# UPCNSL-ABS-PVC-2A.net
KiCad netlist of a schematic drawn in Altium Designer
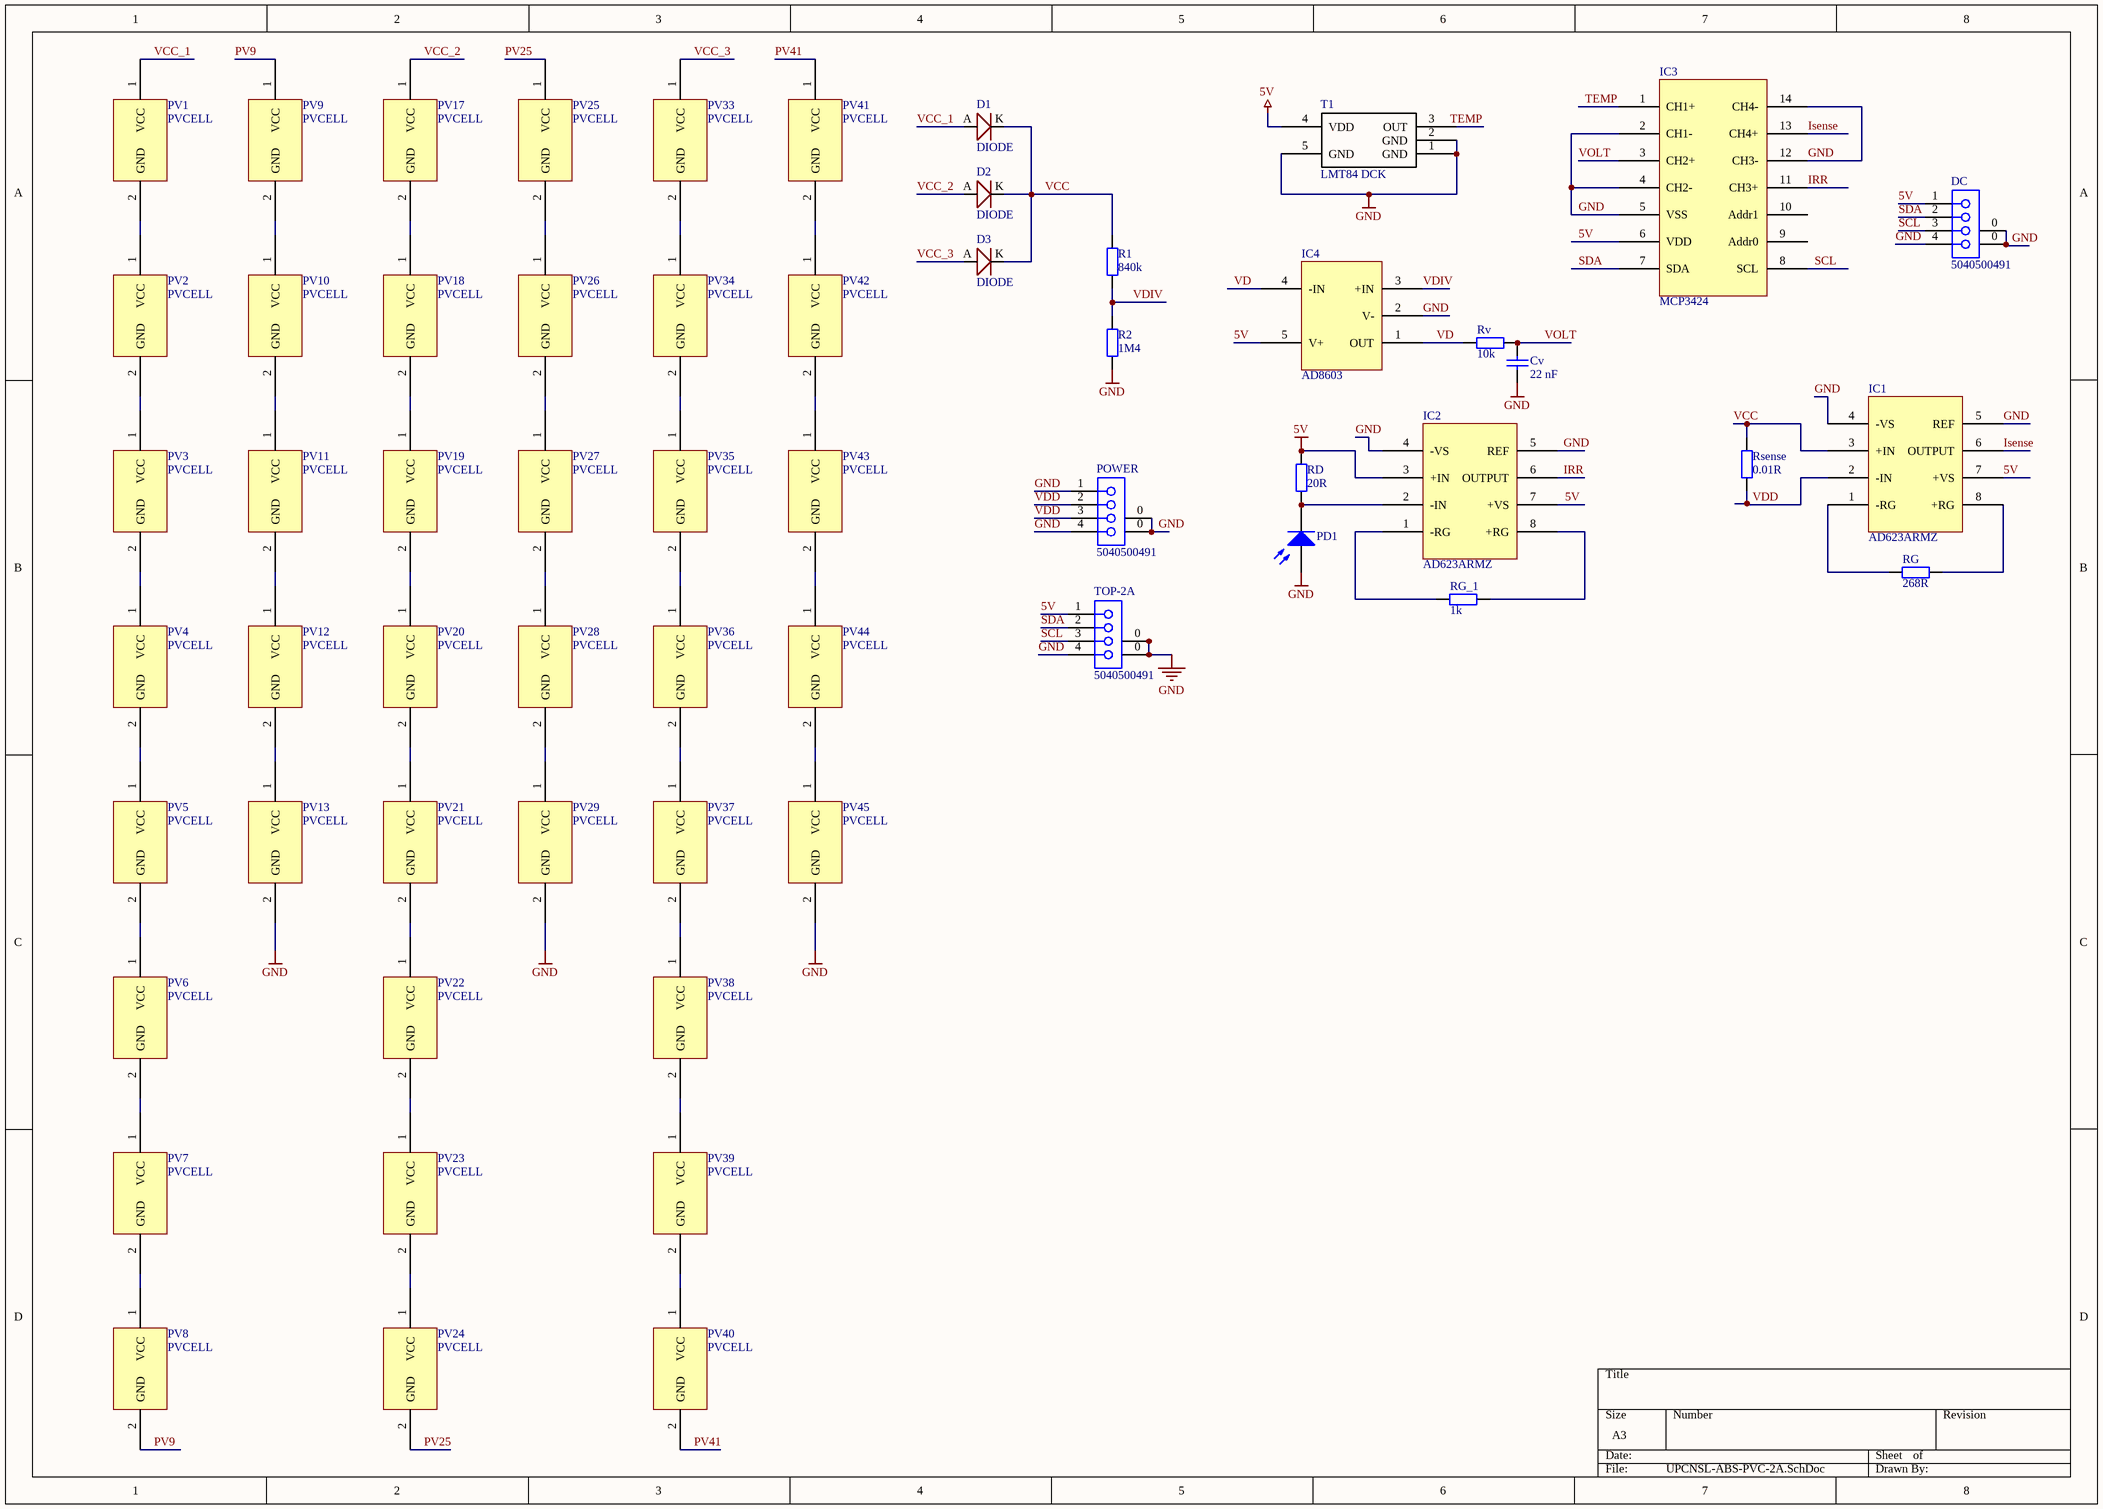
[diagram p0: UPCNSL-ABS-PVC-2A.SchDoc]

(export (version "E")
  (design (tool "Eeschema 10.0.6"))
  (components
    (comp (ref "Cv")
      (value "22 nF")
      (footprint "CAP0603")
      (description "Capacitor")
      (fields (field (name "Comment") "CAP0603"))
      (libsource (lib "UPCNSL-ABS-FLS-ARD_v1.2") (part "CAP0603"))
    )
    (comp (ref "D1")
      (value "DIODE")
      (footprint "(Schottky diode) SODFL160X70-2N")
      (libsource (lib "UPCNSL-ABS-FLS-ARD_v1.2") (part "DIODE"))
    )
    (comp (ref "D2")
      (value "DIODE")
      (footprint "(Schottky diode) SODFL160X70-2N")
      (libsource (lib "UPCNSL-ABS-FLS-ARD_v1.2") (part "DIODE"))
    )
    (comp (ref "D3")
      (value "DIODE")
      (footprint "(Schottky diode) SODFL160X70-2N")
      (libsource (lib "UPCNSL-ABS-FLS-ARD_v1.2") (part "DIODE"))
    )
    (comp (ref "DC")
      (value "5040500491")
      (footprint "5040500491")
      (libsource (lib "3CAT_Connectors") (part "MOLEX_5040500491"))
    )
    (comp (ref "IC1")
      (value "AD623ARMZ")
      (footprint "AD623ARMZ")
      (libsource (lib "UPCNSL-ABS-FLS-PVC") (part "AD623ARMZ"))
    )
    (comp (ref "IC2")
      (value "AD623ARMZ")
      (footprint "AD623ARMZ")
      (libsource (lib "UPCNSL-ABS-FLS-PVC") (part "AD623ARMZ"))
    )
    (comp (ref "IC3")
      (value "MCP3424")
      (footprint "MCP3424")
      (description "18-Bit, Multi-Channel ΔΣ Analog-to-Digital Converter with  I2C")
      (libsource (lib "UPCNSL-ABS-FLS-PVC") (part "MCP3424"))
    )
    (comp (ref "IC4")
      (value "AD8603")
      (footprint "AD8603")
      (libsource (lib "UPCNSL-ABS-FLS-PVC") (part "AD8603"))
    )
    (comp (ref "PD1")
      (value "Photo Sen")
      (footprint "C0805")
      (description "Photosensitive Diode")
      (fields (field (name "PUBLISHER") "Altium Limited"))
      (libsource (lib "Miscellaneous Devices") (part "Photo Sen"))
    )
    (comp (ref "POWER")
      (value "5040500491")
      (footprint "5040500491")
      (libsource (lib "3CAT_Connectors") (part "MOLEX_5040500491"))
    )
    (comp (ref "PV1")
      (value "PVCELL")
      (footprint "PV CELLS")
      (description "IXYS KXOB22-12X1L-ND")
      (libsource (lib "UPCNSL-ABS-FLS-PVC") (part "PVCELLS"))
    )
    (comp (ref "PV2")
      (value "PVCELL")
      (footprint "PV CELLS")
      (description "IXYS KXOB22-12X1L-ND")
      (libsource (lib "UPCNSL-ABS-FLS-PVC") (part "PVCELLS"))
    )
    (comp (ref "PV3")
      (value "PVCELL")
      (footprint "PV CELLS")
      (description "IXYS KXOB22-12X1L-ND")
      (libsource (lib "UPCNSL-ABS-FLS-PVC") (part "PVCELLS"))
    )
    (comp (ref "PV4")
      (value "PVCELL")
      (footprint "PV CELLS")
      (description "IXYS KXOB22-12X1L-ND")
      (libsource (lib "UPCNSL-ABS-FLS-PVC") (part "PVCELLS"))
    )
    (comp (ref "PV5")
      (value "PVCELL")
      (footprint "PV CELLS")
      (description "IXYS KXOB22-12X1L-ND")
      (libsource (lib "UPCNSL-ABS-FLS-PVC") (part "PVCELLS"))
    )
    (comp (ref "PV6")
      (value "PVCELL")
      (footprint "PV CELLS")
      (description "IXYS KXOB22-12X1L-ND")
      (libsource (lib "UPCNSL-ABS-FLS-PVC") (part "PVCELLS"))
    )
    (comp (ref "PV7")
      (value "PVCELL")
      (footprint "PV CELLS")
      (description "IXYS KXOB22-12X1L-ND")
      (libsource (lib "UPCNSL-ABS-FLS-PVC") (part "PVCELLS"))
    )
    (comp (ref "PV8")
      (value "PVCELL")
      (footprint "PV CELLS")
      (description "IXYS KXOB22-12X1L-ND")
      (libsource (lib "UPCNSL-ABS-FLS-PVC") (part "PVCELLS"))
    )
    (comp (ref "PV9")
      (value "PVCELL")
      (footprint "PV CELLS")
      (description "IXYS KXOB22-12X1L-ND")
      (libsource (lib "UPCNSL-ABS-FLS-PVC") (part "PVCELLS"))
    )
    (comp (ref "PV10")
      (value "PVCELL")
      (footprint "PV CELLS")
      (description "IXYS KXOB22-12X1L-ND")
      (libsource (lib "UPCNSL-ABS-FLS-PVC") (part "PVCELLS"))
    )
    (comp (ref "PV11")
      (value "PVCELL")
      (footprint "PV CELLS")
      (description "IXYS KXOB22-12X1L-ND")
      (libsource (lib "UPCNSL-ABS-FLS-PVC") (part "PVCELLS"))
    )
    (comp (ref "PV12")
      (value "PVCELL")
      (footprint "PV CELLS")
      (description "IXYS KXOB22-12X1L-ND")
      (libsource (lib "UPCNSL-ABS-FLS-PVC") (part "PVCELLS"))
    )
    (comp (ref "PV13")
      (value "PVCELL")
      (footprint "PV CELLS")
      (description "IXYS KXOB22-12X1L-ND")
      (libsource (lib "UPCNSL-ABS-FLS-PVC") (part "PVCELLS"))
    )
    (comp (ref "PV17")
      (value "PVCELL")
      (footprint "PV CELLS")
      (description "IXYS KXOB22-12X1L-ND")
      (libsource (lib "UPCNSL-ABS-FLS-PVC") (part "PVCELLS"))
    )
    (comp (ref "PV18")
      (value "PVCELL")
      (footprint "PV CELLS")
      (description "IXYS KXOB22-12X1L-ND")
      (libsource (lib "UPCNSL-ABS-FLS-PVC") (part "PVCELLS"))
    )
    (comp (ref "PV19")
      (value "PVCELL")
      (footprint "PV CELLS")
      (description "IXYS KXOB22-12X1L-ND")
      (libsource (lib "UPCNSL-ABS-FLS-PVC") (part "PVCELLS"))
    )
    (comp (ref "PV20")
      (value "PVCELL")
      (footprint "PV CELLS")
      (description "IXYS KXOB22-12X1L-ND")
      (libsource (lib "UPCNSL-ABS-FLS-PVC") (part "PVCELLS"))
    )
    (comp (ref "PV21")
      (value "PVCELL")
      (footprint "PV CELLS")
      (description "IXYS KXOB22-12X1L-ND")
      (libsource (lib "UPCNSL-ABS-FLS-PVC") (part "PVCELLS"))
    )
    (comp (ref "PV22")
      (value "PVCELL")
      (footprint "PV CELLS")
      (description "IXYS KXOB22-12X1L-ND")
      (libsource (lib "UPCNSL-ABS-FLS-PVC") (part "PVCELLS"))
    )
    (comp (ref "PV23")
      (value "PVCELL")
      (footprint "PV CELLS")
      (description "IXYS KXOB22-12X1L-ND")
      (libsource (lib "UPCNSL-ABS-FLS-PVC") (part "PVCELLS"))
    )
    (comp (ref "PV24")
      (value "PVCELL")
      (footprint "PV CELLS")
      (description "IXYS KXOB22-12X1L-ND")
      (libsource (lib "UPCNSL-ABS-FLS-PVC") (part "PVCELLS"))
    )
    (comp (ref "PV25")
      (value "PVCELL")
      (footprint "PV CELLS")
      (description "IXYS KXOB22-12X1L-ND")
      (libsource (lib "UPCNSL-ABS-FLS-PVC") (part "PVCELLS"))
    )
    (comp (ref "PV26")
      (value "PVCELL")
      (footprint "PV CELLS")
      (description "IXYS KXOB22-12X1L-ND")
      (libsource (lib "UPCNSL-ABS-FLS-PVC") (part "PVCELLS"))
    )
    (comp (ref "PV27")
      (value "PVCELL")
      (footprint "PV CELLS")
      (description "IXYS KXOB22-12X1L-ND")
      (libsource (lib "UPCNSL-ABS-FLS-PVC") (part "PVCELLS"))
    )
    (comp (ref "PV28")
      (value "PVCELL")
      (footprint "PV CELLS")
      (description "IXYS KXOB22-12X1L-ND")
      (libsource (lib "UPCNSL-ABS-FLS-PVC") (part "PVCELLS"))
    )
    (comp (ref "PV29")
      (value "PVCELL")
      (footprint "PV CELLS")
      (description "IXYS KXOB22-12X1L-ND")
      (libsource (lib "UPCNSL-ABS-FLS-PVC") (part "PVCELLS"))
    )
    (comp (ref "PV33")
      (value "PVCELL")
      (footprint "PV CELLS")
      (description "IXYS KXOB22-12X1L-ND")
      (libsource (lib "UPCNSL-ABS-FLS-PVC") (part "PVCELLS"))
    )
    (comp (ref "PV34")
      (value "PVCELL")
      (footprint "PV CELLS")
      (description "IXYS KXOB22-12X1L-ND")
      (libsource (lib "UPCNSL-ABS-FLS-PVC") (part "PVCELLS"))
    )
    (comp (ref "PV35")
      (value "PVCELL")
      (footprint "PV CELLS")
      (description "IXYS KXOB22-12X1L-ND")
      (libsource (lib "UPCNSL-ABS-FLS-PVC") (part "PVCELLS"))
    )
    (comp (ref "PV36")
      (value "PVCELL")
      (footprint "PV CELLS")
      (description "IXYS KXOB22-12X1L-ND")
      (libsource (lib "UPCNSL-ABS-FLS-PVC") (part "PVCELLS"))
    )
    (comp (ref "PV37")
      (value "PVCELL")
      (footprint "PV CELLS")
      (description "IXYS KXOB22-12X1L-ND")
      (libsource (lib "UPCNSL-ABS-FLS-PVC") (part "PVCELLS"))
    )
    (comp (ref "PV38")
      (value "PVCELL")
      (footprint "PV CELLS")
      (description "IXYS KXOB22-12X1L-ND")
      (libsource (lib "UPCNSL-ABS-FLS-PVC") (part "PVCELLS"))
    )
    (comp (ref "PV39")
      (value "PVCELL")
      (footprint "PV CELLS")
      (description "IXYS KXOB22-12X1L-ND")
      (libsource (lib "UPCNSL-ABS-FLS-PVC") (part "PVCELLS"))
    )
    (comp (ref "PV40")
      (value "PVCELL")
      (footprint "PV CELLS")
      (description "IXYS KXOB22-12X1L-ND")
      (libsource (lib "UPCNSL-ABS-FLS-PVC") (part "PVCELLS"))
    )
    (comp (ref "PV41")
      (value "PVCELL")
      (footprint "PV CELLS")
      (description "IXYS KXOB22-12X1L-ND")
      (libsource (lib "UPCNSL-ABS-FLS-PVC") (part "PVCELLS"))
    )
    (comp (ref "PV42")
      (value "PVCELL")
      (footprint "PV CELLS")
      (description "IXYS KXOB22-12X1L-ND")
      (libsource (lib "UPCNSL-ABS-FLS-PVC") (part "PVCELLS"))
    )
    (comp (ref "PV43")
      (value "PVCELL")
      (footprint "PV CELLS")
      (description "IXYS KXOB22-12X1L-ND")
      (libsource (lib "UPCNSL-ABS-FLS-PVC") (part "PVCELLS"))
    )
    (comp (ref "PV44")
      (value "PVCELL")
      (footprint "PV CELLS")
      (description "IXYS KXOB22-12X1L-ND")
      (libsource (lib "UPCNSL-ABS-FLS-PVC") (part "PVCELLS"))
    )
    (comp (ref "PV45")
      (value "PVCELL")
      (footprint "PV CELLS")
      (description "IXYS KXOB22-12X1L-ND")
      (libsource (lib "UPCNSL-ABS-FLS-PVC") (part "PVCELLS"))
    )
    (comp (ref "R1")
      (value "840k")
      (footprint "RES0603")
      (description "Resistor")
      (fields (field (name "Comment") "RES0603"))
      (libsource (lib "UPCNSL-ABS-FLS-ARD_v1.2") (part "RES0603"))
    )
    (comp (ref "R2")
      (value "1M4")
      (footprint "RES0603")
      (description "Resistor")
      (fields (field (name "Comment") "RES0603"))
      (libsource (lib "UPCNSL-ABS-FLS-ARD_v1.2") (part "RES0603"))
    )
    (comp (ref "RD")
      (value "20R")
      (footprint "RES0603")
      (description "Resistor")
      (fields (field (name "Comment") "RES0603"))
      (libsource (lib "UPCNSL-ABS-FLS-ARD_v1.2") (part "RES0603"))
    )
    (comp (ref "RG")
      (value "268R")
      (footprint "RES0603")
      (description "Resistor")
      (fields (field (name "Comment") "RES0603"))
      (libsource (lib "") (part "RES0603_1"))
    )
    (comp (ref "RG_1")
      (value "1k")
      (footprint "RES0603")
      (description "Resistor")
      (fields (field (name "Comment") "RES0603"))
      (libsource (lib "") (part "RES0603_1"))
    )
    (comp (ref "Rsense")
      (value "0.01R")
      (footprint "RES0603")
      (description "Resistor")
      (fields (field (name "Comment") "RES0603"))
      (libsource (lib "UPCNSL-ABS-FLS-ARD_v1.2") (part "RES0603"))
    )
    (comp (ref "Rv")
      (value "10k")
      (footprint "RES0603")
      (description "Resistor")
      (fields (field (name "Comment") "RES0603"))
      (libsource (lib "") (part "RES0603_1"))
    )
    (comp (ref "T1")
      (value "LMT84 DCK")
      (footprint "DCK/SOT65P210X110-5N")
      (libsource (lib "UPCNSL-ABS-FLS-PVC") (part "LMT84 DCK"))
    )
    (comp (ref "TOP-2A")
      (value "5040500491")
      (footprint "5040500491")
      (libsource (lib "3CAT_Connectors") (part "MOLEX_5040500491"))
    )
  )
  (nets
    (net (code "1") (name "/IRR") (class "Default")
      (node (ref "IC2") (pin "6") (pinfunction "OUTPUT_6") (pintype "passive"))
      (node (ref "IC3") (pin "11") (pinfunction "CH3+_11") (pintype "passive"))
    )
    (net (code "2") (name "/Isense") (class "Default")
      (node (ref "IC1") (pin "6") (pinfunction "OUTPUT_6") (pintype "passive"))
      (node (ref "IC3") (pin "13") (pinfunction "CH4+_13") (pintype "passive"))
    )
    (net (code "3") (name "/PV9") (class "Default")
      (node (ref "PV8") (pin "2") (pinfunction "GND_2") (pintype "passive"))
      (node (ref "PV9") (pin "1") (pinfunction "VCC_1") (pintype "passive"))
    )
    (net (code "4") (name "/PV25") (class "Default")
      (node (ref "PV24") (pin "2") (pinfunction "GND_2") (pintype "passive"))
      (node (ref "PV25") (pin "1") (pinfunction "VCC_1") (pintype "passive"))
    )
    (net (code "5") (name "/PV41") (class "Default")
      (node (ref "PV40") (pin "2") (pinfunction "GND_2") (pintype "passive"))
      (node (ref "PV41") (pin "1") (pinfunction "VCC_1") (pintype "passive"))
    )
    (net (code "6") (name "/SCL") (class "Default")
      (node (ref "DC") (pin "3") (pinfunction "3_3") (pintype "passive"))
      (node (ref "IC3") (pin "8") (pinfunction "SCL_8") (pintype "passive"))
      (node (ref "TOP-2A") (pin "3") (pinfunction "3_3") (pintype "passive"))
    )
    (net (code "7") (name "/SDA") (class "Default")
      (node (ref "DC") (pin "2") (pinfunction "2_2") (pintype "passive"))
      (node (ref "IC3") (pin "7") (pinfunction "SDA_7") (pintype "passive"))
      (node (ref "TOP-2A") (pin "2") (pinfunction "2_2") (pintype "passive"))
    )
    (net (code "8") (name "/TEMP") (class "Default")
      (node (ref "IC3") (pin "1") (pinfunction "CH1+_1") (pintype "passive"))
    )
    (net (code "9") (name "/VCC") (class "Default")
      (node (ref "D1") (pin "K") (pinfunction "K_K") (pintype "passive"))
      (node (ref "D2") (pin "K") (pinfunction "K_K") (pintype "passive"))
      (node (ref "D3") (pin "K") (pinfunction "K_K") (pintype "passive"))
      (node (ref "IC1") (pin "3") (pinfunction "+IN_3") (pintype "passive"))
      (node (ref "R1") (pin "2") (pinfunction "2_2") (pintype "passive"))
      (node (ref "Rsense") (pin "2") (pinfunction "2_2") (pintype "passive"))
    )
    (net (code "10") (name "/VCC_1") (class "Default")
      (node (ref "D1") (pin "A") (pinfunction "A_A") (pintype "passive"))
      (node (ref "PV1") (pin "1") (pinfunction "VCC_1") (pintype "passive"))
    )
    (net (code "11") (name "/VCC_2") (class "Default")
      (node (ref "D2") (pin "A") (pinfunction "A_A") (pintype "passive"))
      (node (ref "PV17") (pin "1") (pinfunction "VCC_1") (pintype "passive"))
    )
    (net (code "12") (name "/VCC_3") (class "Default")
      (node (ref "D3") (pin "A") (pinfunction "A_A") (pintype "passive"))
      (node (ref "PV33") (pin "1") (pinfunction "VCC_1") (pintype "passive"))
    )
    (net (code "13") (name "/VD") (class "Default")
      (node (ref "IC4") (pin "1") (pinfunction "OUT_1") (pintype "passive"))
      (node (ref "IC4") (pin "4") (pinfunction "-IN_4") (pintype "passive"))
      (node (ref "Rv") (pin "1") (pinfunction "1_1") (pintype "passive"))
    )
    (net (code "14") (name "/VDD") (class "Default")
      (node (ref "IC1") (pin "2") (pinfunction "-IN_2") (pintype "passive"))
      (node (ref "POWER") (pin "2") (pinfunction "2_2") (pintype "passive"))
      (node (ref "POWER") (pin "3") (pinfunction "3_3") (pintype "passive"))
      (node (ref "Rsense") (pin "1") (pinfunction "1_1") (pintype "passive"))
    )
    (net (code "15") (name "/VDIV") (class "Default")
      (node (ref "IC4") (pin "3") (pinfunction "+IN_3") (pintype "passive"))
      (node (ref "R1") (pin "1") (pinfunction "1_1") (pintype "passive"))
      (node (ref "R2") (pin "2") (pinfunction "2_2") (pintype "passive"))
    )
    (net (code "16") (name "/VOLT") (class "Default")
      (node (ref "Cv") (pin "2") (pinfunction "2_2") (pintype "passive"))
      (node (ref "IC3") (pin "3") (pinfunction "CH2+_3") (pintype "passive"))
      (node (ref "Rv") (pin "2") (pinfunction "2_2") (pintype "passive"))
    )
    (net (code "17") (name "5V") (class "Default")
      (node (ref "DC") (pin "1") (pinfunction "1_1") (pintype "passive"))
      (node (ref "IC1") (pin "7") (pinfunction "+VS_7") (pintype "passive"))
      (node (ref "IC2") (pin "3") (pinfunction "+IN_3") (pintype "passive"))
      (node (ref "IC2") (pin "7") (pinfunction "+VS_7") (pintype "passive"))
      (node (ref "IC3") (pin "6") (pinfunction "VDD_6") (pintype "passive"))
      (node (ref "IC4") (pin "5") (pinfunction "V+_5") (pintype "passive"))
      (node (ref "RD") (pin "2") (pinfunction "2_2") (pintype "passive"))
      (node (ref "T1") (pin "4") (pinfunction "VDD_4") (pintype "passive"))
      (node (ref "TOP-2A") (pin "1") (pinfunction "1_1") (pintype "passive"))
    )
    (net (code "18") (name "GND") (class "Default")
      (node (ref "Cv") (pin "1") (pinfunction "1_1") (pintype "passive"))
      (node (ref "DC") (pin "0") (pinfunction "MH1_0") (pintype "passive"))
      (node (ref "DC") (pin "4") (pinfunction "4_4") (pintype "passive"))
      (node (ref "IC1") (pin "4") (pinfunction "-VS_4") (pintype "passive"))
      (node (ref "IC1") (pin "5") (pinfunction "REF_5") (pintype "passive"))
      (node (ref "IC2") (pin "4") (pinfunction "-VS_4") (pintype "passive"))
      (node (ref "IC2") (pin "5") (pinfunction "REF_5") (pintype "passive"))
      (node (ref "IC3") (pin "12") (pinfunction "CH3-_12") (pintype "passive"))
      (node (ref "IC3") (pin "14") (pinfunction "CH4-_14") (pintype "passive"))
      (node (ref "IC3") (pin "2") (pinfunction "CH1-_2") (pintype "passive"))
      (node (ref "IC3") (pin "4") (pinfunction "CH2-_4") (pintype "passive"))
      (node (ref "IC3") (pin "5") (pinfunction "VSS_5") (pintype "passive"))
      (node (ref "IC4") (pin "2") (pinfunction "V-_2") (pintype "passive"))
      (node (ref "PD1") (pin "1") (pinfunction "A_1") (pintype "passive"))
      (node (ref "POWER") (pin "0") (pinfunction "MH1_0") (pintype "passive"))
      (node (ref "POWER") (pin "1") (pinfunction "1_1") (pintype "passive"))
      (node (ref "POWER") (pin "4") (pinfunction "4_4") (pintype "passive"))
      (node (ref "PV13") (pin "2") (pinfunction "GND_2") (pintype "passive"))
      (node (ref "PV29") (pin "2") (pinfunction "GND_2") (pintype "passive"))
      (node (ref "PV45") (pin "2") (pinfunction "GND_2") (pintype "passive"))
      (node (ref "R2") (pin "1") (pinfunction "1_1") (pintype "passive"))
      (node (ref "T1") (pin "1") (pinfunction "GND_1") (pintype "passive"))
      (node (ref "T1") (pin "2") (pinfunction "GND_2") (pintype "passive"))
      (node (ref "T1") (pin "5") (pinfunction "GND_5") (pintype "passive"))
      (node (ref "TOP-2A") (pin "0") (pinfunction "MH1_0") (pintype "passive"))
      (node (ref "TOP-2A") (pin "4") (pinfunction "4_4") (pintype "passive"))
    )
    (net (code "19") (name "Net-(IC1-+RG)") (class "Default")
      (node (ref "IC1") (pin "8") (pinfunction "+RG_8") (pintype "passive"))
      (node (ref "RG") (pin "2") (pinfunction "2_2") (pintype "passive"))
    )
    (net (code "20") (name "Net-(IC1--RG)") (class "Default")
      (node (ref "IC1") (pin "1") (pinfunction "-RG_1") (pintype "passive"))
      (node (ref "RG") (pin "1") (pinfunction "1_1") (pintype "passive"))
    )
    (net (code "21") (name "Net-(IC2-+RG)") (class "Default")
      (node (ref "IC2") (pin "8") (pinfunction "+RG_8") (pintype "passive"))
      (node (ref "RG_1") (pin "2") (pinfunction "2_2") (pintype "passive"))
    )
    (net (code "22") (name "Net-(IC2--IN)") (class "Default")
      (node (ref "IC2") (pin "2") (pinfunction "-IN_2") (pintype "passive"))
      (node (ref "PD1") (pin "2") (pinfunction "K_2") (pintype "passive"))
      (node (ref "RD") (pin "1") (pinfunction "1_1") (pintype "passive"))
    )
    (net (code "23") (name "Net-(IC2--RG)") (class "Default")
      (node (ref "IC2") (pin "1") (pinfunction "-RG_1") (pintype "passive"))
      (node (ref "RG_1") (pin "1") (pinfunction "1_1") (pintype "passive"))
    )
    (net (code "24") (name "Net-(PV1-GND)") (class "Default")
      (node (ref "PV1") (pin "2") (pinfunction "GND_2") (pintype "passive"))
      (node (ref "PV2") (pin "1") (pinfunction "VCC_1") (pintype "passive"))
    )
    (net (code "25") (name "Net-(PV2-GND)") (class "Default")
      (node (ref "PV2") (pin "2") (pinfunction "GND_2") (pintype "passive"))
      (node (ref "PV3") (pin "1") (pinfunction "VCC_1") (pintype "passive"))
    )
    (net (code "26") (name "Net-(PV3-GND)") (class "Default")
      (node (ref "PV3") (pin "2") (pinfunction "GND_2") (pintype "passive"))
      (node (ref "PV4") (pin "1") (pinfunction "VCC_1") (pintype "passive"))
    )
    (net (code "27") (name "Net-(PV4-GND)") (class "Default")
      (node (ref "PV4") (pin "2") (pinfunction "GND_2") (pintype "passive"))
      (node (ref "PV5") (pin "1") (pinfunction "VCC_1") (pintype "passive"))
    )
    (net (code "28") (name "Net-(PV5-GND)") (class "Default")
      (node (ref "PV5") (pin "2") (pinfunction "GND_2") (pintype "passive"))
      (node (ref "PV6") (pin "1") (pinfunction "VCC_1") (pintype "passive"))
    )
    (net (code "29") (name "Net-(PV6-GND)") (class "Default")
      (node (ref "PV6") (pin "2") (pinfunction "GND_2") (pintype "passive"))
      (node (ref "PV7") (pin "1") (pinfunction "VCC_1") (pintype "passive"))
    )
    (net (code "30") (name "Net-(PV7-GND)") (class "Default")
      (node (ref "PV7") (pin "2") (pinfunction "GND_2") (pintype "passive"))
      (node (ref "PV8") (pin "1") (pinfunction "VCC_1") (pintype "passive"))
    )
    (net (code "31") (name "Net-(PV10-GND)") (class "Default")
      (node (ref "PV10") (pin "2") (pinfunction "GND_2") (pintype "passive"))
      (node (ref "PV11") (pin "1") (pinfunction "VCC_1") (pintype "passive"))
    )
    (net (code "32") (name "Net-(PV10-VCC)") (class "Default")
      (node (ref "PV10") (pin "1") (pinfunction "VCC_1") (pintype "passive"))
      (node (ref "PV9") (pin "2") (pinfunction "GND_2") (pintype "passive"))
    )
    (net (code "33") (name "Net-(PV11-GND)") (class "Default")
      (node (ref "PV11") (pin "2") (pinfunction "GND_2") (pintype "passive"))
      (node (ref "PV12") (pin "1") (pinfunction "VCC_1") (pintype "passive"))
    )
    (net (code "34") (name "Net-(PV12-GND)") (class "Default")
      (node (ref "PV12") (pin "2") (pinfunction "GND_2") (pintype "passive"))
      (node (ref "PV13") (pin "1") (pinfunction "VCC_1") (pintype "passive"))
    )
    (net (code "35") (name "Net-(PV17-GND)") (class "Default")
      (node (ref "PV17") (pin "2") (pinfunction "GND_2") (pintype "passive"))
      (node (ref "PV18") (pin "1") (pinfunction "VCC_1") (pintype "passive"))
    )
    (net (code "36") (name "Net-(PV18-GND)") (class "Default")
      (node (ref "PV18") (pin "2") (pinfunction "GND_2") (pintype "passive"))
      (node (ref "PV19") (pin "1") (pinfunction "VCC_1") (pintype "passive"))
    )
    (net (code "37") (name "Net-(PV19-GND)") (class "Default")
      (node (ref "PV19") (pin "2") (pinfunction "GND_2") (pintype "passive"))
      (node (ref "PV20") (pin "1") (pinfunction "VCC_1") (pintype "passive"))
    )
    (net (code "38") (name "Net-(PV20-GND)") (class "Default")
      (node (ref "PV20") (pin "2") (pinfunction "GND_2") (pintype "passive"))
      (node (ref "PV21") (pin "1") (pinfunction "VCC_1") (pintype "passive"))
    )
    (net (code "39") (name "Net-(PV21-GND)") (class "Default")
      (node (ref "PV21") (pin "2") (pinfunction "GND_2") (pintype "passive"))
      (node (ref "PV22") (pin "1") (pinfunction "VCC_1") (pintype "passive"))
    )
    (net (code "40") (name "Net-(PV22-GND)") (class "Default")
      (node (ref "PV22") (pin "2") (pinfunction "GND_2") (pintype "passive"))
      (node (ref "PV23") (pin "1") (pinfunction "VCC_1") (pintype "passive"))
    )
    (net (code "41") (name "Net-(PV23-GND)") (class "Default")
      (node (ref "PV23") (pin "2") (pinfunction "GND_2") (pintype "passive"))
      (node (ref "PV24") (pin "1") (pinfunction "VCC_1") (pintype "passive"))
    )
    (net (code "42") (name "Net-(PV25-GND)") (class "Default")
      (node (ref "PV25") (pin "2") (pinfunction "GND_2") (pintype "passive"))
      (node (ref "PV26") (pin "1") (pinfunction "VCC_1") (pintype "passive"))
    )
    (net (code "43") (name "Net-(PV26-GND)") (class "Default")
      (node (ref "PV26") (pin "2") (pinfunction "GND_2") (pintype "passive"))
      (node (ref "PV27") (pin "1") (pinfunction "VCC_1") (pintype "passive"))
    )
    (net (code "44") (name "Net-(PV27-GND)") (class "Default")
      (node (ref "PV27") (pin "2") (pinfunction "GND_2") (pintype "passive"))
      (node (ref "PV28") (pin "1") (pinfunction "VCC_1") (pintype "passive"))
    )
    (net (code "45") (name "Net-(PV28-GND)") (class "Default")
      (node (ref "PV28") (pin "2") (pinfunction "GND_2") (pintype "passive"))
      (node (ref "PV29") (pin "1") (pinfunction "VCC_1") (pintype "passive"))
    )
    (net (code "46") (name "Net-(PV33-GND)") (class "Default")
      (node (ref "PV33") (pin "2") (pinfunction "GND_2") (pintype "passive"))
      (node (ref "PV34") (pin "1") (pinfunction "VCC_1") (pintype "passive"))
    )
    (net (code "47") (name "Net-(PV34-GND)") (class "Default")
      (node (ref "PV34") (pin "2") (pinfunction "GND_2") (pintype "passive"))
      (node (ref "PV35") (pin "1") (pinfunction "VCC_1") (pintype "passive"))
    )
    (net (code "48") (name "Net-(PV35-GND)") (class "Default")
      (node (ref "PV35") (pin "2") (pinfunction "GND_2") (pintype "passive"))
      (node (ref "PV36") (pin "1") (pinfunction "VCC_1") (pintype "passive"))
    )
    (net (code "49") (name "Net-(PV36-GND)") (class "Default")
      (node (ref "PV36") (pin "2") (pinfunction "GND_2") (pintype "passive"))
      (node (ref "PV37") (pin "1") (pinfunction "VCC_1") (pintype "passive"))
    )
    (net (code "50") (name "Net-(PV37-GND)") (class "Default")
      (node (ref "PV37") (pin "2") (pinfunction "GND_2") (pintype "passive"))
      (node (ref "PV38") (pin "1") (pinfunction "VCC_1") (pintype "passive"))
    )
    (net (code "51") (name "Net-(PV38-GND)") (class "Default")
      (node (ref "PV38") (pin "2") (pinfunction "GND_2") (pintype "passive"))
      (node (ref "PV39") (pin "1") (pinfunction "VCC_1") (pintype "passive"))
    )
    (net (code "52") (name "Net-(PV39-GND)") (class "Default")
      (node (ref "PV39") (pin "2") (pinfunction "GND_2") (pintype "passive"))
      (node (ref "PV40") (pin "1") (pinfunction "VCC_1") (pintype "passive"))
    )
    (net (code "53") (name "Net-(PV41-GND)") (class "Default")
      (node (ref "PV41") (pin "2") (pinfunction "GND_2") (pintype "passive"))
      (node (ref "PV42") (pin "1") (pinfunction "VCC_1") (pintype "passive"))
    )
    (net (code "54") (name "Net-(PV42-GND)") (class "Default")
      (node (ref "PV42") (pin "2") (pinfunction "GND_2") (pintype "passive"))
      (node (ref "PV43") (pin "1") (pinfunction "VCC_1") (pintype "passive"))
    )
    (net (code "55") (name "Net-(PV43-GND)") (class "Default")
      (node (ref "PV43") (pin "2") (pinfunction "GND_2") (pintype "passive"))
      (node (ref "PV44") (pin "1") (pinfunction "VCC_1") (pintype "passive"))
    )
    (net (code "56") (name "Net-(PV44-GND)") (class "Default")
      (node (ref "PV44") (pin "2") (pinfunction "GND_2") (pintype "passive"))
      (node (ref "PV45") (pin "1") (pinfunction "VCC_1") (pintype "passive"))
    )
    (net (code "57") (name "unconnected-(IC3-Addr0-Pad9)") (class "Default")
      (node (ref "IC3") (pin "9") (pinfunction "Addr0_9") (pintype "passive"))
    )
    (net (code "58") (name "unconnected-(IC3-Addr1-Pad10)") (class "Default")
      (node (ref "IC3") (pin "10") (pinfunction "Addr1_10") (pintype "passive"))
    )
    (net (code "59") (name "unconnected-(T1-OUT-Pad3)") (class "Default")
      (node (ref "T1") (pin "3") (pinfunction "OUT_3") (pintype "passive"))
    )
  )
)
